# zero_cross_fire_triac.net
KiCad netlist of a schematic drawn in EAGLE
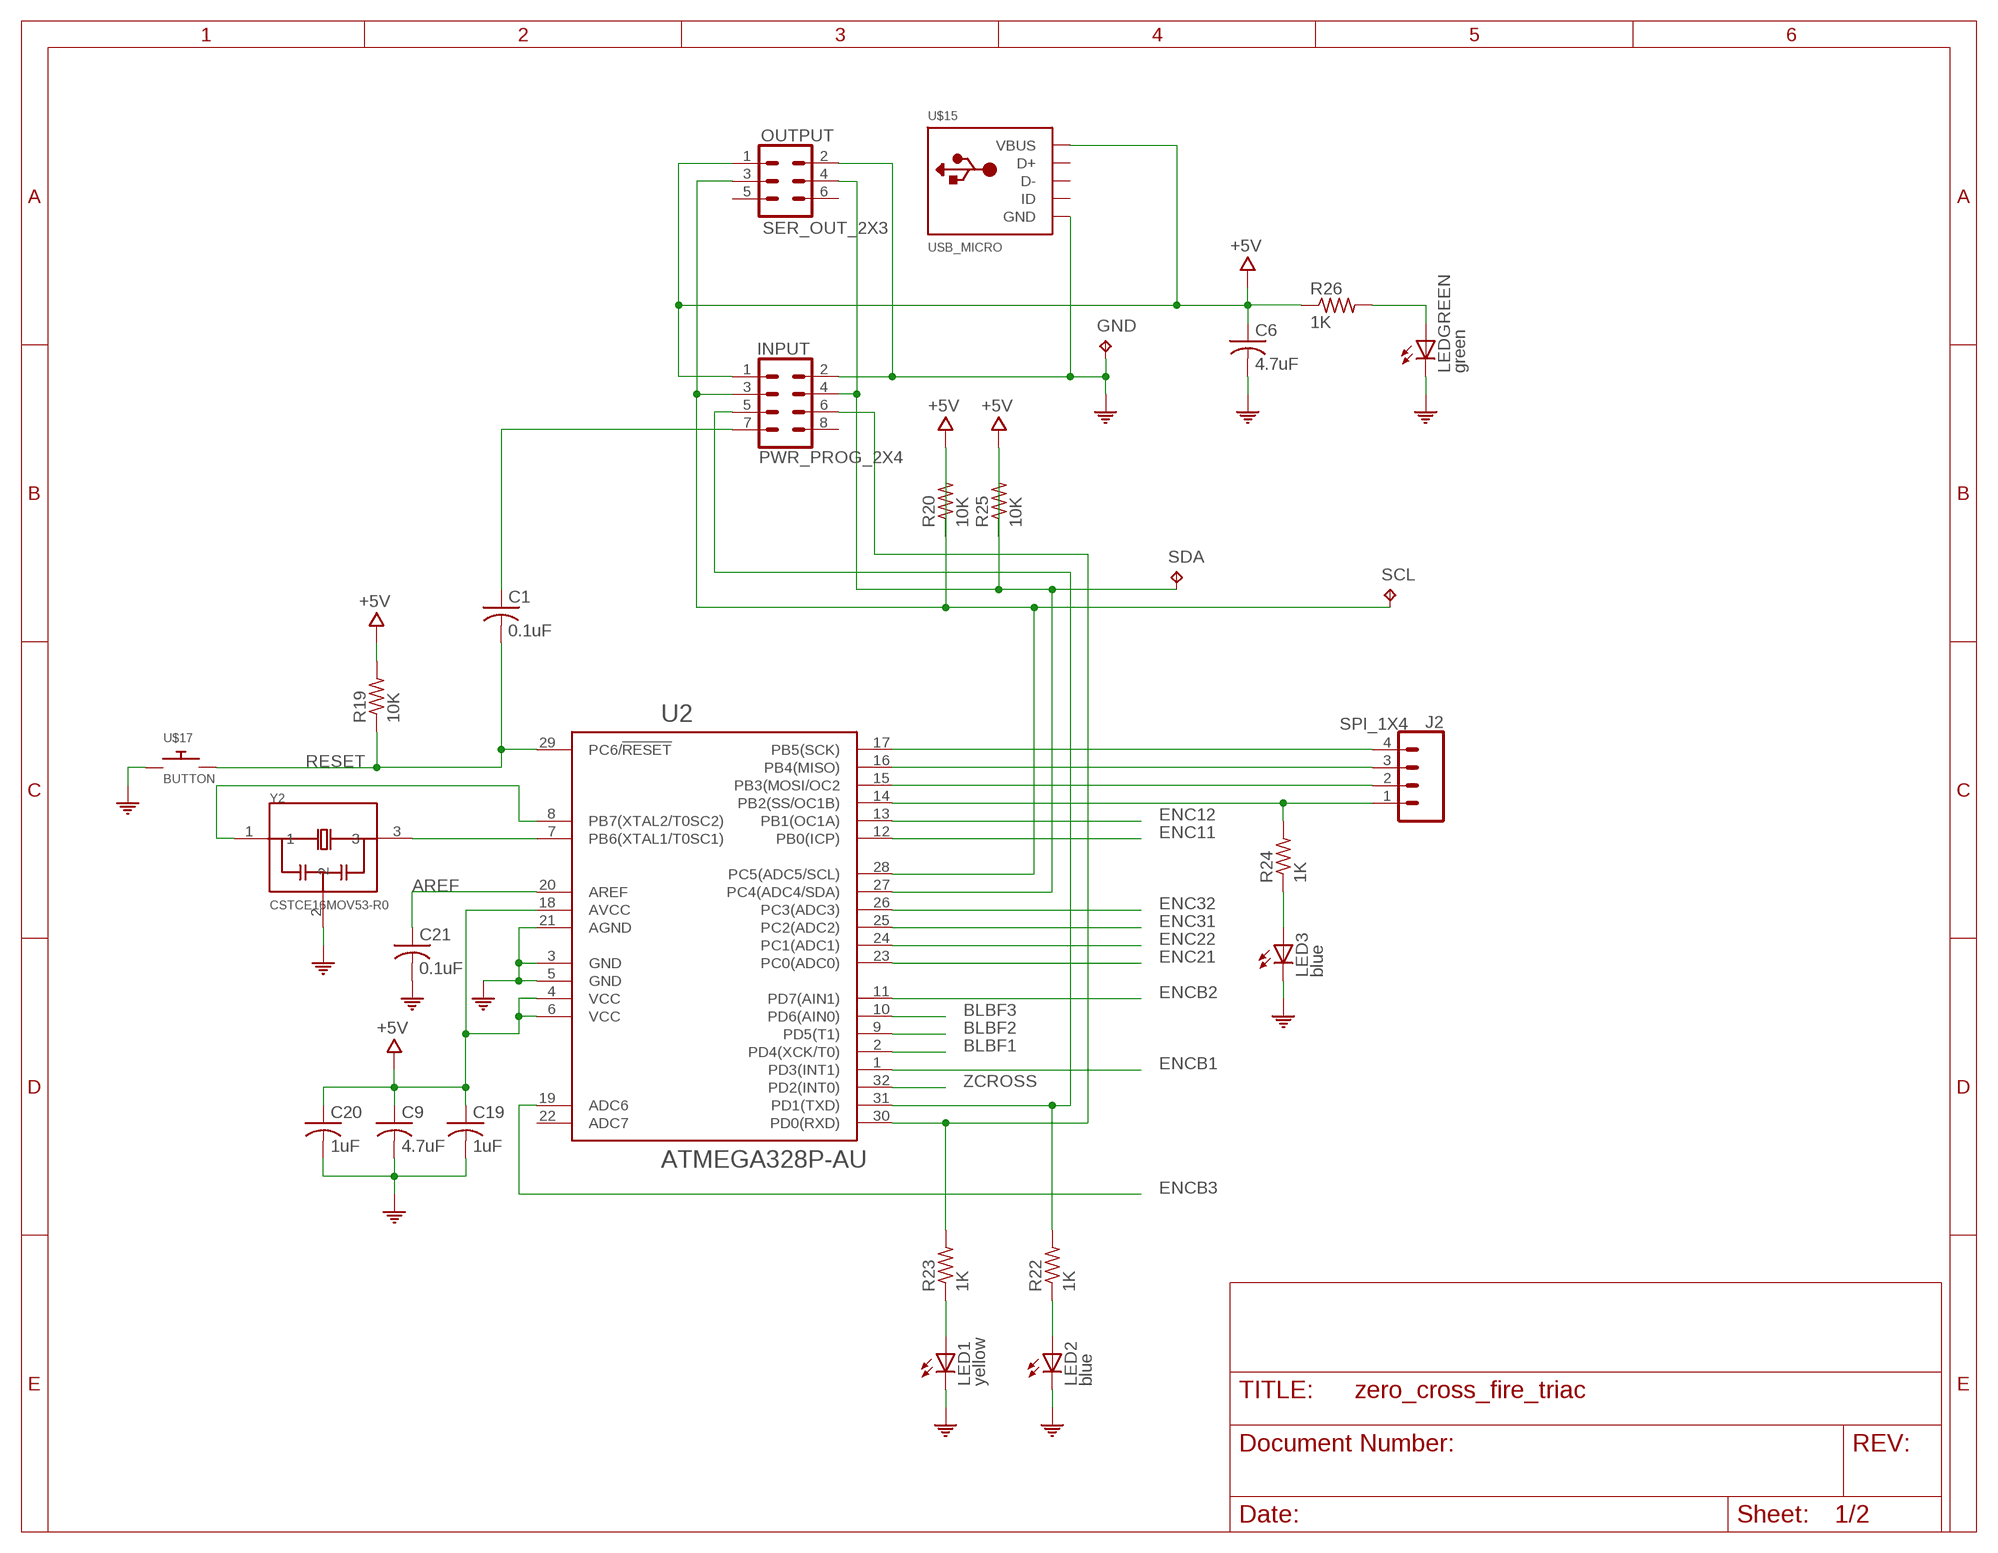
[diagram p0: schematic, sheet 1]
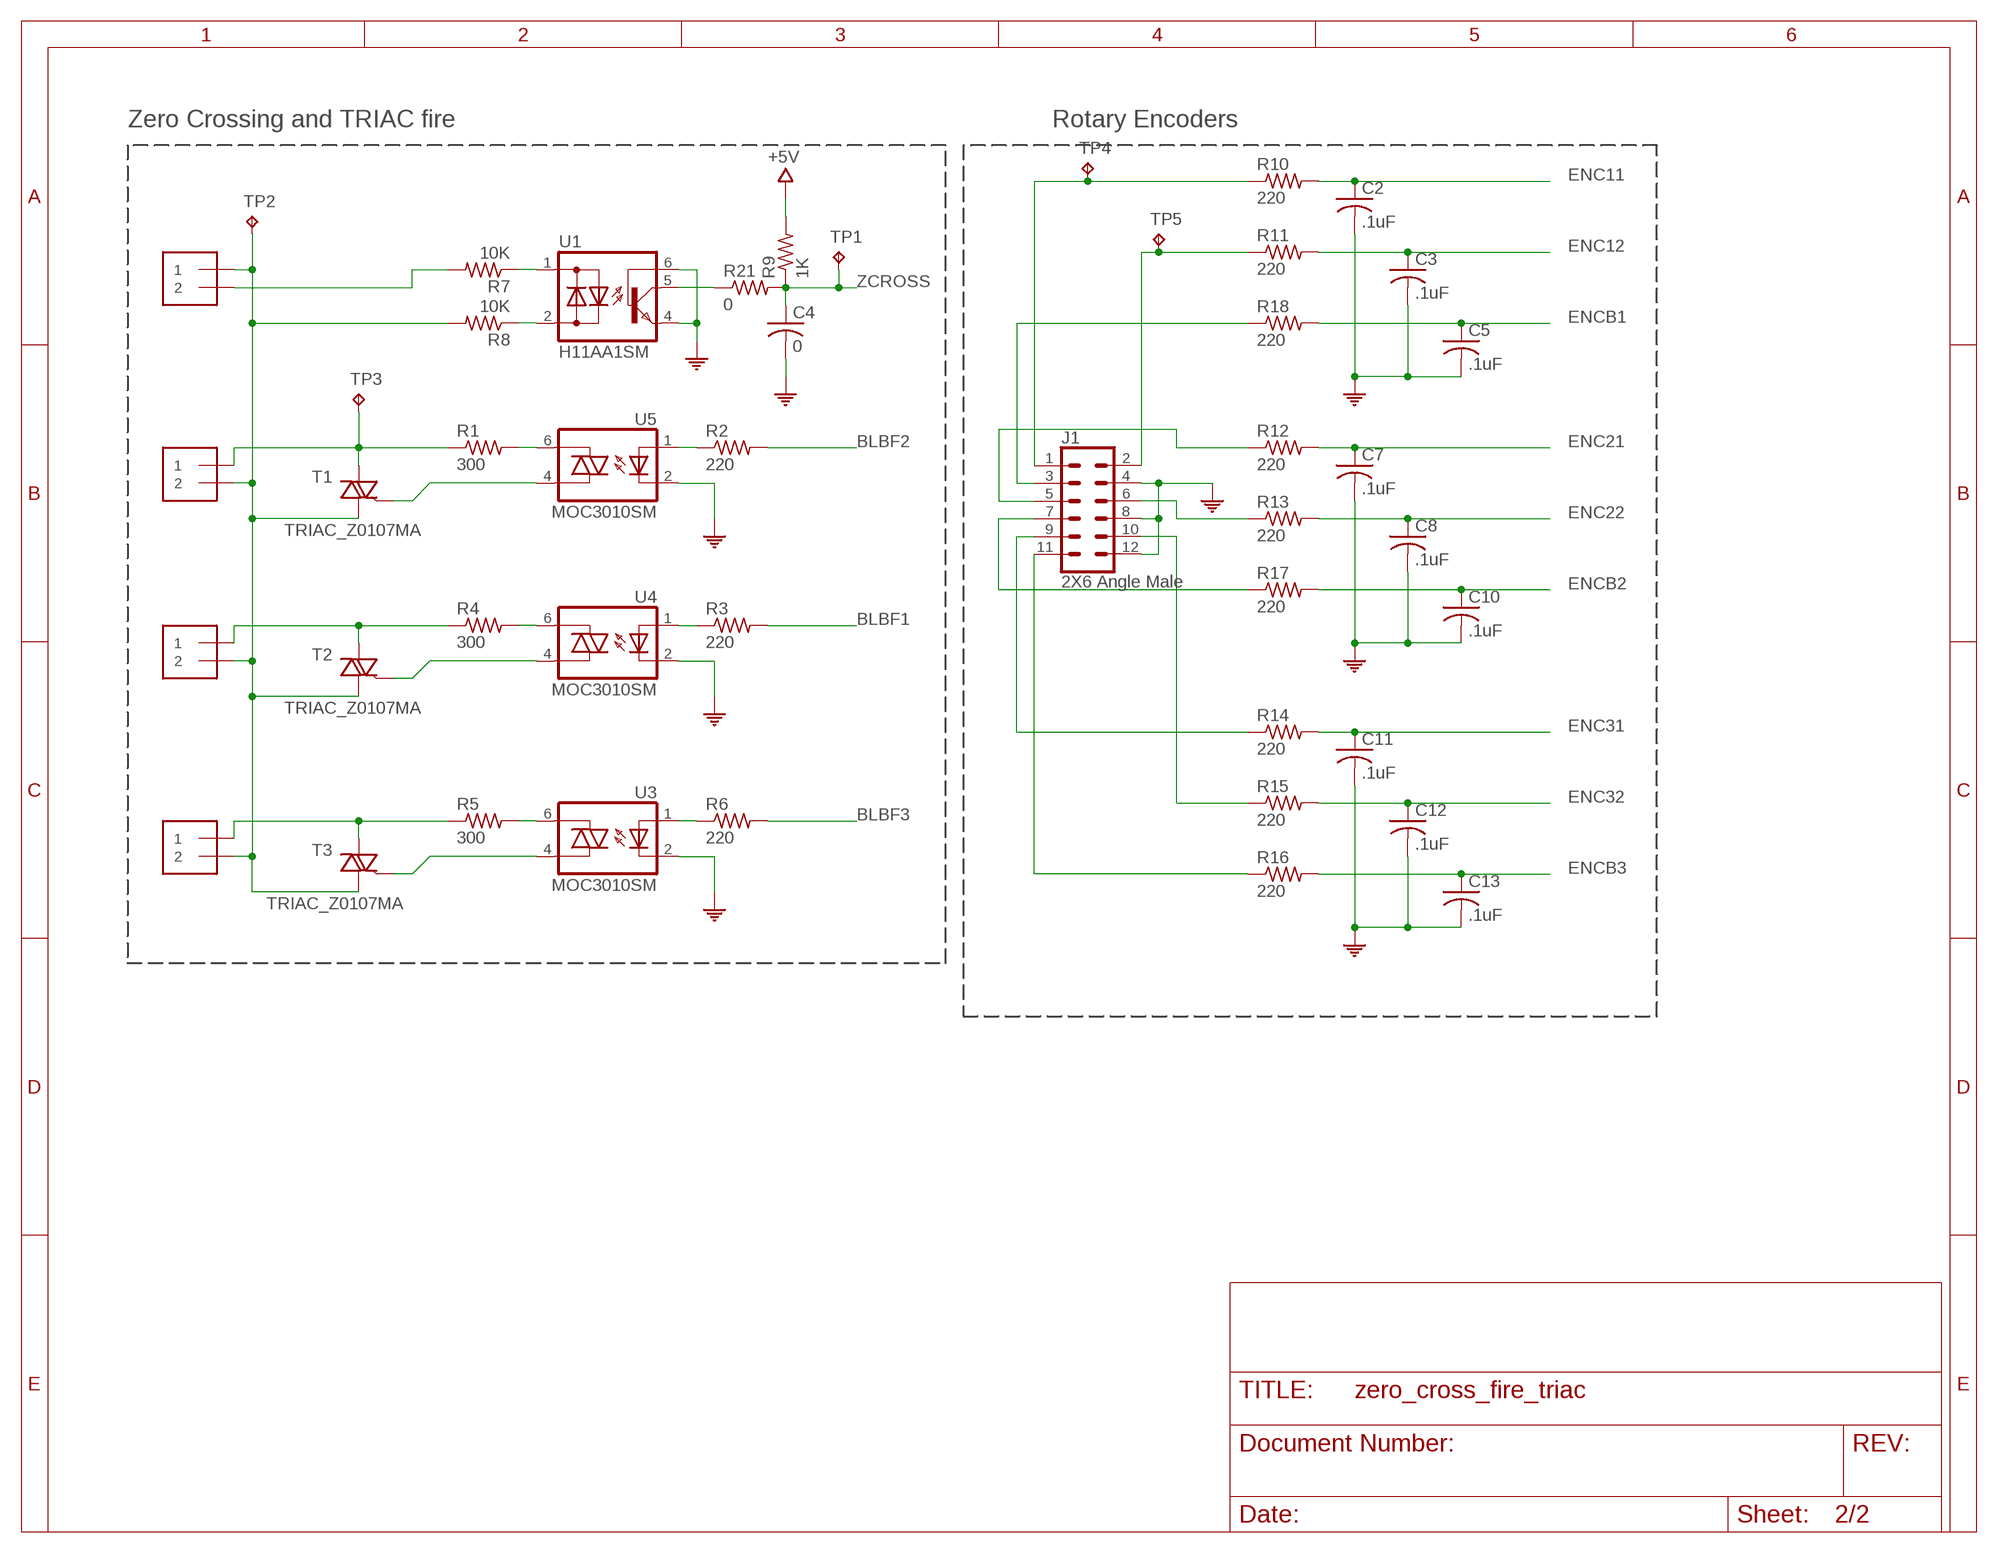
[diagram p1: schematic, sheet 2]

(export (version "E")
  (design (tool "Eeschema 10.0.6"))
  (components
    (comp (ref "C1")
      (value "0.1uF")
      (footprint "eagle-import:C0805")
      (fields (field (name "MF") "TDK") (field (name "MP") "C2012X7R2A104K125AA"))
      (libsource (lib "eagle-import") (part "CAP_C2012X7R2A104K125AA"))
    )
    (comp (ref "C6")
      (value "4.7uF")
      (footprint "eagle-import:C0805")
      (fields (field (name "MF") "KEMET") (field (name "MP") "C0805C475J4RACAUTO"))
      (libsource (lib "eagle-import") (part "CAP_C0805C475J4RACAUTO"))
    )
    (comp (ref "C9")
      (value "4.7uF")
      (footprint "eagle-import:C0805")
      (fields (field (name "MF") "KEMET") (field (name "MP") "C0805C475J4RACAUTO"))
      (libsource (lib "eagle-import") (part "CAP_C0805C475J4RACAUTO"))
    )
    (comp (ref "C19")
      (value "1uF")
      (footprint "eagle-import:C0805")
      (fields (field (name "MF") "TDK") (field (name "MP") " CGA4J1X8R1E105M125AE"))
      (libsource (lib "eagle-import") (part "CAP_CGA4J1X8R1E105M125AE"))
    )
    (comp (ref "C20")
      (value "1uF")
      (footprint "eagle-import:C0805")
      (fields (field (name "MF") "TDK") (field (name "MP") " CGA4J1X8R1E105M125AE"))
      (libsource (lib "eagle-import") (part "CAP_CGA4J1X8R1E105M125AE"))
    )
    (comp (ref "C21")
      (value "0.1uF")
      (footprint "eagle-import:C0805")
      (fields (field (name "MF") "TDK") (field (name "MP") "C2012X7R2A104K125AA"))
      (libsource (lib "eagle-import") (part "CAP_C2012X7R2A104K125AA"))
    )
    (comp (ref "GND")
      (value "TEST_POINT")
      (footprint "eagle-import:TEST")
      (fields (field (name "MF") "Keystone Electronics") (field (name "MP") " 5016"))
      (libsource (lib "eagle-import") (part "TEST_POINT"))
    )
    (comp (ref "INPUT")
      (value "PWR_PROG_2X4")
      (footprint "eagle-import:2X04")
      (fields (field (name "MF") "Adafruit") (field (name "MP") "2x4"))
      (libsource (lib "eagle-import") (part "PWR_PROG_2X4"))
    )
    (comp (ref "J2")
      (value "SPI_1X4")
      (footprint "eagle-import:1X04-BIG")
      (fields (field (name "MF") "adafruit") (field (name "MP") "1x4 "))
      (libsource (lib "eagle-import") (part "SPI_1X4"))
    )
    (comp (ref "LED1")
      (value "yellow")
      (footprint "eagle-import:LED1")
      (fields (field (name "MF") "Kingbright") (field (name "MP") "APTD2012LSYCK"))
      (libsource (lib "eagle-import") (part "LED_APTD2012LSYCK"))
    )
    (comp (ref "LED2")
      (value "blue")
      (footprint "eagle-import:LED1")
      (fields (field (name "MF") "Kingbright") (field (name "MP") "APTD2012LQBC/D"))
      (libsource (lib "eagle-import") (part "LED_APTD2012LQBC"))
    )
    (comp (ref "LED3")
      (value "blue")
      (footprint "eagle-import:LED1")
      (fields (field (name "MF") "Kingbright") (field (name "MP") "APTD2012LQBC/D"))
      (libsource (lib "eagle-import") (part "LED_APTD2012LQBC"))
    )
    (comp (ref "LEDGREEN")
      (value "green")
      (footprint "eagle-import:LED1")
      (fields (field (name "MF") "Kingbright") (field (name "MP") "APTD2012LZGCK"))
      (libsource (lib "eagle-import") (part "LED_APTD2012LZGCK"))
    )
    (comp (ref "OUTPUT")
      (value "SER_OUT_2X3")
      (footprint "eagle-import:2X03")
      (fields (field (name "MF") "adafruit") (field (name "MP") "2x3 female break away"))
      (libsource (lib "eagle-import") (part "SER_OUT_2X3"))
    )
    (comp (ref "R19")
      (value "10K")
      (footprint "eagle-import:R0805")
      (fields (field (name "MF") "Yageo") (field (name "MP") "RC0805JR-7W10KL"))
      (libsource (lib "eagle-import") (part "RESISTOR_RC0805JR-7W10KL"))
    )
    (comp (ref "R20")
      (value "10K")
      (footprint "eagle-import:R0805")
      (fields (field (name "MF") "Yageo") (field (name "MP") "RC0805JR-7W10KL"))
      (libsource (lib "eagle-import") (part "RESISTOR_RC0805JR-7W10KL"))
    )
    (comp (ref "R22")
      (value "1K")
      (footprint "eagle-import:R0805")
      (fields (field (name "MF") "Yageo") (field (name "MP") "RC0805JR-7W1KL"))
      (libsource (lib "eagle-import") (part "RESISTOR_RC0805JR-7W1KL"))
    )
    (comp (ref "R23")
      (value "1K")
      (footprint "eagle-import:R0805")
      (fields (field (name "MF") "Yageo") (field (name "MP") "RC0805JR-7W1KL"))
      (libsource (lib "eagle-import") (part "RESISTOR_RC0805JR-7W1KL"))
    )
    (comp (ref "R24")
      (value "1K")
      (footprint "eagle-import:R0805")
      (fields (field (name "MF") "Yageo") (field (name "MP") "RC0805JR-7W1KL"))
      (libsource (lib "eagle-import") (part "RESISTOR_RC0805JR-7W1KL"))
    )
    (comp (ref "R25")
      (value "10K")
      (footprint "eagle-import:R0805")
      (fields (field (name "MF") "Yageo") (field (name "MP") "RC0805JR-7W10KL"))
      (libsource (lib "eagle-import") (part "RESISTOR_RC0805JR-7W10KL"))
    )
    (comp (ref "R26")
      (value "1K")
      (footprint "eagle-import:R0805")
      (fields (field (name "MF") "Yageo") (field (name "MP") "RC0805JR-7W1KL"))
      (libsource (lib "eagle-import") (part "RESISTOR_RC0805JR-7W1KL"))
    )
    (comp (ref "SCL")
      (value "TEST_POINT")
      (footprint "eagle-import:TEST")
      (fields (field (name "MF") "Keystone Electronics") (field (name "MP") " 5016"))
      (libsource (lib "eagle-import") (part "TEST_POINT"))
    )
    (comp (ref "SDA")
      (value "TEST_POINT")
      (footprint "eagle-import:TEST")
      (fields (field (name "MF") "Keystone Electronics") (field (name "MP") " 5016"))
      (libsource (lib "eagle-import") (part "TEST_POINT"))
    )
    (comp (ref "U$15")
      (value "USB_MICRO")
      (footprint "eagle-import:USB-MICRO-SMD-CUSTOM")
      (libsource (lib "eagle-import") (part "USB_MICRO"))
    )
    (comp (ref "U$17")
      (value "BUTTON")
      (footprint "eagle-import:PUSHBUTTON")
      (fields (field (name "MF") "E-Switch") (field (name "MP") " LL3301FF065QJ"))
      (libsource (lib "eagle-import") (part "BUTTON"))
    )
    (comp (ref "U2")
      (value "ATMEGA328P-AU")
      (footprint "eagle-import:QFP80P900X900X120-32N")
      (fields (field (name "MF") "Microchip"))
      (libsource (lib "eagle-import") (part "ATMEGA328P-AU"))
    )
    (comp (ref "Y2")
      (value "CSTCE16MOV53-R0")
      (footprint "eagle-import:OSC_CSTCE8M00G55-R0")
      (fields (field (name "MF") "Murata Electronics") (field (name "MP") "CSTCE16M0V53-R0"))
      (libsource (lib "eagle-import") (part "CSTCE16MOV53-R0"))
    )
    (comp (ref "BLB1")
      (value "SCREW_BLOCK_2PIN")
      (footprint "eagle-import:1X2-200MIL")
      (libsource (lib "eagle-import") (part "SCREW_BLOCK_2PIN"))
    )
    (comp (ref "BLB2")
      (value "SCREW_BLOCK_2PIN")
      (footprint "eagle-import:1X2-200MIL")
      (libsource (lib "eagle-import") (part "SCREW_BLOCK_2PIN"))
    )
    (comp (ref "BLB3")
      (value "SCREW_BLOCK_2PIN")
      (footprint "eagle-import:1X2-200MIL")
      (libsource (lib "eagle-import") (part "SCREW_BLOCK_2PIN"))
    )
    (comp (ref "C2")
      (value ".1uF")
      (footprint "eagle-import:C0805")
      (fields (field (name "MF") "TDK") (field (name "MP") "C2012X7R2A104K125AA"))
      (libsource (lib "eagle-import") (part "CAP_C2012X7R2A104K125AA"))
    )
    (comp (ref "C3")
      (value ".1uF")
      (footprint "eagle-import:C0805")
      (fields (field (name "MF") "TDK") (field (name "MP") "C2012X7R2A104K125AA"))
      (libsource (lib "eagle-import") (part "CAP_C2012X7R2A104K125AA"))
    )
    (comp (ref "C4")
      (value "0")
      (footprint "eagle-import:C0805")
      (fields (field (name "MF") "TDK") (field (name "MP") "C2012X7R2A104K125AA"))
      (libsource (lib "eagle-import") (part "CAP_C2012X7R2A104K125AA"))
    )
    (comp (ref "C5")
      (value ".1uF")
      (footprint "eagle-import:C0805")
      (fields (field (name "MF") "TDK") (field (name "MP") "C2012X7R2A104K125AA"))
      (libsource (lib "eagle-import") (part "CAP_C2012X7R2A104K125AA"))
    )
    (comp (ref "C7")
      (value ".1uF")
      (footprint "eagle-import:C0805")
      (fields (field (name "MF") "TDK") (field (name "MP") "C2012X7R2A104K125AA"))
      (libsource (lib "eagle-import") (part "CAP_C2012X7R2A104K125AA"))
    )
    (comp (ref "C8")
      (value ".1uF")
      (footprint "eagle-import:C0805")
      (fields (field (name "MF") "TDK") (field (name "MP") "C2012X7R2A104K125AA"))
      (libsource (lib "eagle-import") (part "CAP_C2012X7R2A104K125AA"))
    )
    (comp (ref "C10")
      (value ".1uF")
      (footprint "eagle-import:C0805")
      (fields (field (name "MF") "TDK") (field (name "MP") "C2012X7R2A104K125AA"))
      (libsource (lib "eagle-import") (part "CAP_C2012X7R2A104K125AA"))
    )
    (comp (ref "C11")
      (value ".1uF")
      (footprint "eagle-import:C0805")
      (fields (field (name "MF") "TDK") (field (name "MP") "C2012X7R2A104K125AA"))
      (libsource (lib "eagle-import") (part "CAP_C2012X7R2A104K125AA"))
    )
    (comp (ref "C12")
      (value ".1uF")
      (footprint "eagle-import:C0805")
      (fields (field (name "MF") "TDK") (field (name "MP") "C2012X7R2A104K125AA"))
      (libsource (lib "eagle-import") (part "CAP_C2012X7R2A104K125AA"))
    )
    (comp (ref "C13")
      (value ".1uF")
      (footprint "eagle-import:C0805")
      (fields (field (name "MF") "TDK") (field (name "MP") "C2012X7R2A104K125AA"))
      (libsource (lib "eagle-import") (part "CAP_C2012X7R2A104K125AA"))
    )
    (comp (ref "J1")
      (value "2X6 Angle Male")
      (footprint "eagle-import:2X06")
      (fields (field (name "MF") "Adafruit") (field (name "MP") "2X6 angle"))
      (libsource (lib "eagle-import") (part "ROT_ENCODE_2X6"))
    )
    (comp (ref "MAIN")
      (value "SCREW_BLOCK_2PIN")
      (footprint "eagle-import:1X2-200MIL")
      (libsource (lib "eagle-import") (part "SCREW_BLOCK_2PIN"))
    )
    (comp (ref "R1")
      (value "300")
      (footprint "eagle-import:R1210")
      (fields (field (name "MF") "ROHM Semiconductor") (field (name "MP") " KTR25JZPF3000"))
      (libsource (lib "eagle-import") (part "RESISTOR_KTR25JZPF3000"))
    )
    (comp (ref "R2")
      (value "220")
      (footprint "eagle-import:R0805")
      (fields (field (name "MF") "ROHM Semiconductor") (field (name "MP") "ESR10EZPF2200"))
      (libsource (lib "eagle-import") (part "RESISTOR_ESR10EZPF"))
    )
    (comp (ref "R3")
      (value "220")
      (footprint "eagle-import:R0805")
      (fields (field (name "MF") "ROHM Semiconductor") (field (name "MP") "ESR10EZPF2200"))
      (libsource (lib "eagle-import") (part "RESISTOR_ESR10EZPF"))
    )
    (comp (ref "R4")
      (value "300")
      (footprint "eagle-import:R1210")
      (fields (field (name "MF") "ROHM Semiconductor") (field (name "MP") " KTR25JZPF3000"))
      (libsource (lib "eagle-import") (part "RESISTOR_KTR25JZPF3000"))
    )
    (comp (ref "R5")
      (value "300")
      (footprint "eagle-import:R1210")
      (fields (field (name "MF") "ROHM Semiconductor") (field (name "MP") " KTR25JZPF3000"))
      (libsource (lib "eagle-import") (part "RESISTOR_KTR25JZPF3000"))
    )
    (comp (ref "R6")
      (value "220")
      (footprint "eagle-import:R0805")
      (fields (field (name "MF") "ROHM Semiconductor") (field (name "MP") "ESR10EZPF2200"))
      (libsource (lib "eagle-import") (part "RESISTOR_ESR10EZPF"))
    )
    (comp (ref "R7")
      (value "10K")
      (footprint "eagle-import:RLTR50")
      (fields (field (name "MF") "ROHM Semiconductor") (field (name "MP") " LTR50UZPJ103"))
      (libsource (lib "eagle-import") (part "RESISTOR_LTR50UZPJ"))
    )
    (comp (ref "R8")
      (value "10K")
      (footprint "eagle-import:RLTR50")
      (fields (field (name "MF") "ROHM Semiconductor") (field (name "MP") " LTR50UZPJ103"))
      (libsource (lib "eagle-import") (part "RESISTOR_LTR50UZPJ"))
    )
    (comp (ref "R9")
      (value "1K")
      (footprint "eagle-import:R0805")
      (fields (field (name "MF") "Yageo") (field (name "MP") "RC0805JR-7W1KL"))
      (libsource (lib "eagle-import") (part "RESISTOR_RC0805JR-7W1KL"))
    )
    (comp (ref "R10")
      (value "220")
      (footprint "eagle-import:R0805")
      (fields (field (name "MF") "ROHM Semiconductor") (field (name "MP") "ESR10EZPF2200"))
      (libsource (lib "eagle-import") (part "RESISTOR_ESR10EZPF"))
    )
    (comp (ref "R11")
      (value "220")
      (footprint "eagle-import:R0805")
      (fields (field (name "MF") "ROHM Semiconductor") (field (name "MP") "ESR10EZPF2200"))
      (libsource (lib "eagle-import") (part "RESISTOR_ESR10EZPF"))
    )
    (comp (ref "R12")
      (value "220")
      (footprint "eagle-import:R0805")
      (fields (field (name "MF") "ROHM Semiconductor") (field (name "MP") "ESR10EZPF2200"))
      (libsource (lib "eagle-import") (part "RESISTOR_ESR10EZPF"))
    )
    (comp (ref "R13")
      (value "220")
      (footprint "eagle-import:R0805")
      (fields (field (name "MF") "ROHM Semiconductor") (field (name "MP") "ESR10EZPF2200"))
      (libsource (lib "eagle-import") (part "RESISTOR_ESR10EZPF"))
    )
    (comp (ref "R14")
      (value "220")
      (footprint "eagle-import:R0805")
      (fields (field (name "MF") "ROHM Semiconductor") (field (name "MP") "ESR10EZPF2200"))
      (libsource (lib "eagle-import") (part "RESISTOR_ESR10EZPF"))
    )
    (comp (ref "R15")
      (value "220")
      (footprint "eagle-import:R0805")
      (fields (field (name "MF") "ROHM Semiconductor") (field (name "MP") "ESR10EZPF2200"))
      (libsource (lib "eagle-import") (part "RESISTOR_ESR10EZPF"))
    )
    (comp (ref "R16")
      (value "220")
      (footprint "eagle-import:R0805")
      (fields (field (name "MF") "ROHM Semiconductor") (field (name "MP") "ESR10EZPF2200"))
      (libsource (lib "eagle-import") (part "RESISTOR_ESR10EZPF"))
    )
    (comp (ref "R17")
      (value "220")
      (footprint "eagle-import:R0805")
      (fields (field (name "MF") "ROHM Semiconductor") (field (name "MP") "ESR10EZPF2200"))
      (libsource (lib "eagle-import") (part "RESISTOR_ESR10EZPF"))
    )
    (comp (ref "R18")
      (value "220")
      (footprint "eagle-import:R0805")
      (fields (field (name "MF") "ROHM Semiconductor") (field (name "MP") "ESR10EZPF2200"))
      (libsource (lib "eagle-import") (part "RESISTOR_ESR10EZPF"))
    )
    (comp (ref "R21")
      (value "0")
      (footprint "eagle-import:R0805")
      (fields (field (name "MF") "ROHM Semiconductor") (field (name "MP") "ESR10EZPF2200"))
      (libsource (lib "eagle-import") (part "RESISTOR_ESR10EZPF"))
    )
    (comp (ref "T1")
      (value "TRIAC_Z0107MA")
      (footprint "eagle-import:TO92")
      (fields (field (name "MF") "STMicroelectronics") (field (name "MP") "Z0107MA 5AL2"))
      (libsource (lib "eagle-import") (part "TRIAC_Z0107MA"))
    )
    (comp (ref "T2")
      (value "TRIAC_Z0107MA")
      (footprint "eagle-import:TO92")
      (fields (field (name "MF") "STMicroelectronics") (field (name "MP") "Z0107MA 5AL2"))
      (libsource (lib "eagle-import") (part "TRIAC_Z0107MA"))
    )
    (comp (ref "T3")
      (value "TRIAC_Z0107MA")
      (footprint "eagle-import:TO92")
      (fields (field (name "MF") "STMicroelectronics") (field (name "MP") "Z0107MA 5AL2"))
      (libsource (lib "eagle-import") (part "TRIAC_Z0107MA"))
    )
    (comp (ref "TP1")
      (value "TEST_POINT")
      (footprint "eagle-import:TEST")
      (fields (field (name "MF") "Keystone Electronics") (field (name "MP") " 5016"))
      (libsource (lib "eagle-import") (part "TEST_POINT"))
    )
    (comp (ref "TP2")
      (value "TEST_POINT")
      (footprint "eagle-import:TEST")
      (fields (field (name "MF") "Keystone Electronics") (field (name "MP") " 5016"))
      (libsource (lib "eagle-import") (part "TEST_POINT"))
    )
    (comp (ref "TP3")
      (value "TEST_POINT")
      (footprint "eagle-import:TEST")
      (fields (field (name "MF") "Keystone Electronics") (field (name "MP") " 5016"))
      (libsource (lib "eagle-import") (part "TEST_POINT"))
    )
    (comp (ref "TP4")
      (value "TEST_POINT")
      (footprint "eagle-import:TEST")
      (fields (field (name "MF") "Keystone Electronics") (field (name "MP") " 5016"))
      (libsource (lib "eagle-import") (part "TEST_POINT"))
    )
    (comp (ref "TP5")
      (value "TEST_POINT")
      (footprint "eagle-import:TEST")
      (fields (field (name "MF") "Keystone Electronics") (field (name "MP") " 5016"))
      (libsource (lib "eagle-import") (part "TEST_POINT"))
    )
    (comp (ref "U1")
      (value "H11AA1SM")
      (footprint "eagle-import:DIL6-SMD")
      (fields (field (name "MF") " ON Semiconductor / Fairchild"))
      (libsource (lib "eagle-import") (part "H11AA1SM"))
    )
    (comp (ref "U3")
      (value "MOC3010SM")
      (footprint "eagle-import:DIL6-SMD")
      (fields (field (name "MF") "ON Semiconductor / Fairchild"))
      (libsource (lib "eagle-import") (part "MOC3010SM"))
    )
    (comp (ref "U4")
      (value "MOC3010SM")
      (footprint "eagle-import:DIL6-SMD")
      (fields (field (name "MF") "ON Semiconductor / Fairchild"))
      (libsource (lib "eagle-import") (part "MOC3010SM"))
    )
    (comp (ref "U5")
      (value "MOC3010SM")
      (footprint "eagle-import:DIL6-SMD")
      (fields (field (name "MF") "ON Semiconductor / Fairchild"))
      (libsource (lib "eagle-import") (part "MOC3010SM"))
    )
  )
  (nets
    (net (code "1") (name "+5V") (class "Default")
      (node (ref "C19") (pin "1") (pinfunction "1_1") (pintype "passive"))
      (node (ref "C20") (pin "1") (pinfunction "1_1") (pintype "passive"))
      (node (ref "C6") (pin "1") (pinfunction "1_1") (pintype "passive"))
      (node (ref "C9") (pin "1") (pinfunction "1_1") (pintype "passive"))
      (node (ref "INPUT") (pin "1") (pinfunction "1_1") (pintype "passive"))
      (node (ref "OUTPUT") (pin "1") (pinfunction "1_1") (pintype "bidirectional"))
      (node (ref "R19") (pin "2") (pinfunction "2_2") (pintype "passive"))
      (node (ref "R20") (pin "1") (pinfunction "1_1") (pintype "passive"))
      (node (ref "R25") (pin "1") (pinfunction "1_1") (pintype "passive"))
      (node (ref "R26") (pin "1") (pinfunction "1_1") (pintype "passive"))
      (node (ref "R9") (pin "2") (pinfunction "2_2") (pintype "passive"))
      (node (ref "U$15") (pin "VBUS") (pinfunction "VBUS_VBUS") (pintype "power_in"))
      (node (ref "U2") (pin "18") (pinfunction "AVCC_18") (pintype "power_in"))
      (node (ref "U2") (pin "4") (pinfunction "VCC_4") (pintype "power_in"))
      (node (ref "U2") (pin "6") (pinfunction "VCC_6") (pintype "power_in"))
    )
    (net (code "2") (name "AREF") (class "Default")
      (node (ref "C21") (pin "1") (pinfunction "1_1") (pintype "passive"))
      (node (ref "U2") (pin "20") (pinfunction "AREF_20") (pintype "input"))
    )
    (net (code "3") (name "BLBF1") (class "Default")
      (node (ref "R3") (pin "2") (pinfunction "2_2") (pintype "passive"))
      (node (ref "U2") (pin "2") (pinfunction "PD4(XCK/T0)_2") (pintype "bidirectional"))
    )
    (net (code "4") (name "BLBF2") (class "Default")
      (node (ref "R2") (pin "2") (pinfunction "2_2") (pintype "passive"))
      (node (ref "U2") (pin "9") (pinfunction "PD5(T1)_9") (pintype "bidirectional"))
    )
    (net (code "5") (name "BLBF3") (class "Default")
      (node (ref "R6") (pin "2") (pinfunction "2_2") (pintype "passive"))
      (node (ref "U2") (pin "10") (pinfunction "PD6(AIN0)_10") (pintype "bidirectional"))
    )
    (net (code "6") (name "COM") (class "Default")
      (node (ref "C10") (pin "2") (pinfunction "2_2") (pintype "passive"))
      (node (ref "C11") (pin "2") (pinfunction "2_2") (pintype "passive"))
      (node (ref "C12") (pin "2") (pinfunction "2_2") (pintype "passive"))
      (node (ref "C13") (pin "2") (pinfunction "2_2") (pintype "passive"))
      (node (ref "C19") (pin "2") (pinfunction "2_2") (pintype "passive"))
      (node (ref "C2") (pin "2") (pinfunction "2_2") (pintype "passive"))
      (node (ref "C20") (pin "2") (pinfunction "2_2") (pintype "passive"))
      (node (ref "C21") (pin "2") (pinfunction "2_2") (pintype "passive"))
      (node (ref "C3") (pin "2") (pinfunction "2_2") (pintype "passive"))
      (node (ref "C4") (pin "2") (pinfunction "2_2") (pintype "passive"))
      (node (ref "C5") (pin "2") (pinfunction "2_2") (pintype "passive"))
      (node (ref "C6") (pin "2") (pinfunction "2_2") (pintype "passive"))
      (node (ref "C7") (pin "2") (pinfunction "2_2") (pintype "passive"))
      (node (ref "C8") (pin "2") (pinfunction "2_2") (pintype "passive"))
      (node (ref "C9") (pin "2") (pinfunction "2_2") (pintype "passive"))
      (node (ref "GND") (pin "1") (pinfunction "TP_1") (pintype "input"))
      (node (ref "INPUT") (pin "2") (pinfunction "2_2") (pintype "passive"))
      (node (ref "J1") (pin "12") (pinfunction "12_12") (pintype "passive"))
      (node (ref "J1") (pin "4") (pinfunction "4_4") (pintype "passive"))
      (node (ref "J1") (pin "8") (pinfunction "8_8") (pintype "passive"))
      (node (ref "LED1") (pin "1") (pinfunction "C_1") (pintype "passive"))
      (node (ref "LED2") (pin "1") (pinfunction "C_1") (pintype "passive"))
      (node (ref "LED3") (pin "1") (pinfunction "C_1") (pintype "passive"))
      (node (ref "LEDGREEN") (pin "1") (pinfunction "C_1") (pintype "passive"))
      (node (ref "OUTPUT") (pin "2") (pinfunction "2_2") (pintype "bidirectional"))
      (node (ref "U$15") (pin "GND") (pinfunction "GND_GND") (pintype "power_in"))
      (node (ref "U$15") (pin "SHIELD1") (pinfunction "GND_SHIELD1") (pintype "power_in"))
      (node (ref "U$15") (pin "SHIELD2") (pinfunction "GND_SHIELD2") (pintype "power_in"))
      (node (ref "U$15") (pin "SHIELD3") (pinfunction "GND_SHIELD3") (pintype "power_in"))
      (node (ref "U$17") (pin "1") (pinfunction "P$1_1") (pintype "passive"))
      (node (ref "U$17") (pin "2") (pinfunction "P$1_2") (pintype "passive"))
      (node (ref "U1") (pin "4") (pinfunction "E_4") (pintype "passive"))
      (node (ref "U1") (pin "6") (pinfunction "B_6") (pintype "passive"))
      (node (ref "U2") (pin "21") (pinfunction "AGND_21") (pintype "power_in"))
      (node (ref "U2") (pin "3") (pinfunction "GND_3") (pintype "power_in"))
      (node (ref "U2") (pin "5") (pinfunction "GND_5") (pintype "power_in"))
      (node (ref "U3") (pin "2") (pinfunction "C_2") (pintype "passive"))
      (node (ref "U4") (pin "2") (pinfunction "C_2") (pintype "passive"))
      (node (ref "U5") (pin "2") (pinfunction "C_2") (pintype "passive"))
      (node (ref "Y2") (pin "2") (pinfunction "2_2") (pintype "power_in"))
    )
    (net (code "7") (name "ENC11") (class "Default")
      (node (ref "C2") (pin "1") (pinfunction "1_1") (pintype "passive"))
      (node (ref "R10") (pin "2") (pinfunction "2_2") (pintype "passive"))
      (node (ref "U2") (pin "12") (pinfunction "PB0(ICP)_12") (pintype "bidirectional"))
    )
    (net (code "8") (name "ENC12") (class "Default")
      (node (ref "C3") (pin "1") (pinfunction "1_1") (pintype "passive"))
      (node (ref "R11") (pin "2") (pinfunction "2_2") (pintype "passive"))
      (node (ref "U2") (pin "13") (pinfunction "PB1(OC1A)_13") (pintype "bidirectional"))
    )
    (net (code "9") (name "ENC21") (class "Default")
      (node (ref "C7") (pin "1") (pinfunction "1_1") (pintype "passive"))
      (node (ref "R12") (pin "2") (pinfunction "2_2") (pintype "passive"))
      (node (ref "U2") (pin "23") (pinfunction "PC0(ADC0)_23") (pintype "bidirectional"))
    )
    (net (code "10") (name "ENC22") (class "Default")
      (node (ref "C8") (pin "1") (pinfunction "1_1") (pintype "passive"))
      (node (ref "R13") (pin "2") (pinfunction "2_2") (pintype "passive"))
      (node (ref "U2") (pin "24") (pinfunction "PC1(ADC1)_24") (pintype "bidirectional"))
    )
    (net (code "11") (name "ENC31") (class "Default")
      (node (ref "C11") (pin "1") (pinfunction "1_1") (pintype "passive"))
      (node (ref "R14") (pin "2") (pinfunction "2_2") (pintype "passive"))
      (node (ref "U2") (pin "25") (pinfunction "PC2(ADC2)_25") (pintype "bidirectional"))
    )
    (net (code "12") (name "ENC32") (class "Default")
      (node (ref "C12") (pin "1") (pinfunction "1_1") (pintype "passive"))
      (node (ref "R15") (pin "2") (pinfunction "2_2") (pintype "passive"))
      (node (ref "U2") (pin "26") (pinfunction "PC3(ADC3)_26") (pintype "bidirectional"))
    )
    (net (code "13") (name "ENCB1") (class "Default")
      (node (ref "C5") (pin "1") (pinfunction "1_1") (pintype "passive"))
      (node (ref "R18") (pin "2") (pinfunction "2_2") (pintype "passive"))
      (node (ref "U2") (pin "1") (pinfunction "PD3(INT1)_1") (pintype "bidirectional"))
    )
    (net (code "14") (name "ENCB2") (class "Default")
      (node (ref "C10") (pin "1") (pinfunction "1_1") (pintype "passive"))
      (node (ref "R17") (pin "2") (pinfunction "2_2") (pintype "passive"))
      (node (ref "U2") (pin "11") (pinfunction "PD7(AIN1)_11") (pintype "bidirectional"))
    )
    (net (code "15") (name "ENCB3") (class "Default")
      (node (ref "C13") (pin "1") (pinfunction "1_1") (pintype "passive"))
      (node (ref "R16") (pin "2") (pinfunction "2_2") (pintype "passive"))
      (node (ref "U2") (pin "19") (pinfunction "ADC6_19") (pintype "bidirectional"))
    )
    (net (code "16") (name "Net-(BLB1-1)") (class "Default")
      (node (ref "BLB1") (pin "2") (pinfunction "1_2") (pintype "passive"))
      (node (ref "R4") (pin "1") (pinfunction "1_1") (pintype "passive"))
      (node (ref "T2") (pin "3") (pinfunction "A2_3") (pintype "passive"))
    )
    (net (code "17") (name "Net-(BLB1-2)") (class "Default")
      (node (ref "BLB1") (pin "1") (pinfunction "2_1") (pintype "passive"))
      (node (ref "BLB2") (pin "1") (pinfunction "2_1") (pintype "passive"))
      (node (ref "BLB3") (pin "1") (pinfunction "2_1") (pintype "passive"))
      (node (ref "MAIN") (pin "2") (pinfunction "1_2") (pintype "passive"))
      (node (ref "R8") (pin "P$2") (pinfunction "2_P$2") (pintype "passive"))
      (node (ref "T1") (pin "1") (pinfunction "A1_1") (pintype "passive"))
      (node (ref "T2") (pin "1") (pinfunction "A1_1") (pintype "passive"))
      (node (ref "T3") (pin "1") (pinfunction "A1_1") (pintype "passive"))
      (node (ref "TP2") (pin "1") (pinfunction "TP_1") (pintype "input"))
    )
    (net (code "18") (name "Net-(BLB2-1)") (class "Default")
      (node (ref "BLB2") (pin "2") (pinfunction "1_2") (pintype "passive"))
      (node (ref "R1") (pin "1") (pinfunction "1_1") (pintype "passive"))
      (node (ref "T1") (pin "3") (pinfunction "A2_3") (pintype "passive"))
      (node (ref "TP3") (pin "1") (pinfunction "TP_1") (pintype "input"))
    )
    (net (code "19") (name "Net-(BLB3-1)") (class "Default")
      (node (ref "BLB3") (pin "2") (pinfunction "1_2") (pintype "passive"))
      (node (ref "R5") (pin "1") (pinfunction "1_1") (pintype "passive"))
      (node (ref "T3") (pin "3") (pinfunction "A2_3") (pintype "passive"))
    )
    (net (code "20") (name "Net-(C1-Pad1)") (class "Default")
      (node (ref "C1") (pin "1") (pinfunction "1_1") (pintype "passive"))
      (node (ref "INPUT") (pin "7") (pinfunction "7_7") (pintype "passive"))
    )
    (net (code "21") (name "Net-(J1-Pad3)") (class "Default")
      (node (ref "J1") (pin "3") (pinfunction "3_3") (pintype "passive"))
      (node (ref "R18") (pin "1") (pinfunction "1_1") (pintype "passive"))
    )
    (net (code "22") (name "Net-(J1-Pad5)") (class "Default")
      (node (ref "J1") (pin "5") (pinfunction "5_5") (pintype "passive"))
      (node (ref "R12") (pin "1") (pinfunction "1_1") (pintype "passive"))
    )
    (net (code "23") (name "Net-(J1-Pad6)") (class "Default")
      (node (ref "J1") (pin "6") (pinfunction "6_6") (pintype "passive"))
      (node (ref "R13") (pin "1") (pinfunction "1_1") (pintype "passive"))
    )
    (net (code "24") (name "Net-(J1-Pad7)") (class "Default")
      (node (ref "J1") (pin "7") (pinfunction "7_7") (pintype "passive"))
      (node (ref "R17") (pin "1") (pinfunction "1_1") (pintype "passive"))
    )
    (net (code "25") (name "Net-(J1-Pad9)") (class "Default")
      (node (ref "J1") (pin "9") (pinfunction "9_9") (pintype "passive"))
      (node (ref "R14") (pin "1") (pinfunction "1_1") (pintype "passive"))
    )
    (net (code "26") (name "Net-(J1-Pad10)") (class "Default")
      (node (ref "J1") (pin "10") (pinfunction "10_10") (pintype "passive"))
      (node (ref "R15") (pin "1") (pinfunction "1_1") (pintype "passive"))
    )
    (net (code "27") (name "Net-(J1-Pad11)") (class "Default")
      (node (ref "J1") (pin "11") (pinfunction "11_11") (pintype "passive"))
      (node (ref "R16") (pin "1") (pinfunction "1_1") (pintype "passive"))
    )
    (net (code "28") (name "Net-(LED1-A)") (class "Default")
      (node (ref "LED1") (pin "2") (pinfunction "A_2") (pintype "passive"))
      (node (ref "R23") (pin "1") (pinfunction "1_1") (pintype "passive"))
    )
    (net (code "29") (name "Net-(LED2-A)") (class "Default")
      (node (ref "LED2") (pin "2") (pinfunction "A_2") (pintype "passive"))
      (node (ref "R22") (pin "1") (pinfunction "1_1") (pintype "passive"))
    )
    (net (code "30") (name "Net-(LED3-A)") (class "Default")
      (node (ref "LED3") (pin "2") (pinfunction "A_2") (pintype "passive"))
      (node (ref "R24") (pin "1") (pinfunction "1_1") (pintype "passive"))
    )
    (net (code "31") (name "Net-(LEDGREEN-A)") (class "Default")
      (node (ref "LEDGREEN") (pin "2") (pinfunction "A_2") (pintype "passive"))
      (node (ref "R26") (pin "2") (pinfunction "2_2") (pintype "passive"))
    )
    (net (code "32") (name "Net-(MAIN-2)") (class "Default")
      (node (ref "MAIN") (pin "1") (pinfunction "2_1") (pintype "passive"))
      (node (ref "R7") (pin "P$2") (pinfunction "2_P$2") (pintype "passive"))
    )
    (net (code "33") (name "Net-(R7-1)") (class "Default")
      (node (ref "R7") (pin "P$1") (pinfunction "1_P$1") (pintype "passive"))
      (node (ref "U1") (pin "1") (pinfunction "AC1_1") (pintype "passive"))
    )
    (net (code "34") (name "Net-(R8-1)") (class "Default")
      (node (ref "R8") (pin "P$1") (pinfunction "1_P$1") (pintype "passive"))
      (node (ref "U1") (pin "2") (pinfunction "AC2_2") (pintype "passive"))
    )
    (net (code "35") (name "Net-(SCL-TP)") (class "Default")
      (node (ref "INPUT") (pin "3") (pinfunction "3_3") (pintype "passive"))
      (node (ref "OUTPUT") (pin "3") (pinfunction "3_3") (pintype "bidirectional"))
      (node (ref "R20") (pin "2") (pinfunction "2_2") (pintype "passive"))
      (node (ref "SCL") (pin "1") (pinfunction "TP_1") (pintype "input"))
      (node (ref "U2") (pin "28") (pinfunction "PC5(ADC5/SCL)_28") (pintype "bidirectional"))
    )
    (net (code "36") (name "Net-(SDA-TP)") (class "Default")
      (node (ref "INPUT") (pin "4") (pinfunction "4_4") (pintype "passive"))
      (node (ref "OUTPUT") (pin "4") (pinfunction "4_4") (pintype "bidirectional"))
      (node (ref "R25") (pin "2") (pinfunction "2_2") (pintype "passive"))
      (node (ref "SDA") (pin "1") (pinfunction "TP_1") (pintype "input"))
      (node (ref "U2") (pin "27") (pinfunction "PC4(ADC4/SDA)_27") (pintype "bidirectional"))
    )
    (net (code "37") (name "Net-(T1-G)") (class "Default")
      (node (ref "T1") (pin "2") (pinfunction "G_2") (pintype "passive"))
      (node (ref "U5") (pin "4") (pinfunction "A1_4") (pintype "passive"))
    )
    (net (code "38") (name "Net-(T2-G)") (class "Default")
      (node (ref "T2") (pin "2") (pinfunction "G_2") (pintype "passive"))
      (node (ref "U4") (pin "4") (pinfunction "A1_4") (pintype "passive"))
    )
    (net (code "39") (name "Net-(T3-G)") (class "Default")
      (node (ref "T3") (pin "2") (pinfunction "G_2") (pintype "passive"))
      (node (ref "U3") (pin "4") (pinfunction "A1_4") (pintype "passive"))
    )
    (net (code "40") (name "Net-(TP4-TP)") (class "Default")
      (node (ref "J1") (pin "1") (pinfunction "1_1") (pintype "passive"))
      (node (ref "R10") (pin "1") (pinfunction "1_1") (pintype "passive"))
      (node (ref "TP4") (pin "1") (pinfunction "TP_1") (pintype "input"))
    )
    (net (code "41") (name "Net-(TP5-TP)") (class "Default")
      (node (ref "J1") (pin "2") (pinfunction "2_2") (pintype "passive"))
      (node (ref "R11") (pin "1") (pinfunction "1_1") (pintype "passive"))
      (node (ref "TP5") (pin "1") (pinfunction "TP_1") (pintype "input"))
    )
    (net (code "42") (name "Net-(U1-C)") (class "Default")
      (node (ref "R21") (pin "1") (pinfunction "1_1") (pintype "passive"))
      (node (ref "U1") (pin "5") (pinfunction "C_5") (pintype "passive"))
    )
    (net (code "43") (name "Net-(U2-PB2(SS{slash}OC1B))") (class "Default")
      (node (ref "J2") (pin "1") (pinfunction "1_1") (pintype "passive"))
      (node (ref "R24") (pin "2") (pinfunction "2_2") (pintype "passive"))
      (node (ref "U2") (pin "14") (pinfunction "PB2(SS/OC1B)_14") (pintype "bidirectional"))
    )
    (net (code "44") (name "Net-(U2-PB3(MOSI{slash}OC2)") (class "Default")
      (node (ref "J2") (pin "2") (pinfunction "2_2") (pintype "passive"))
      (node (ref "U2") (pin "15") (pinfunction "PB3(MOSI/OC2_15") (pintype "bidirectional"))
    )
    (net (code "45") (name "Net-(U2-PB4(MISO))") (class "Default")
      (node (ref "J2") (pin "3") (pinfunction "3_3") (pintype "passive"))
      (node (ref "U2") (pin "16") (pinfunction "PB4(MISO)_16") (pintype "bidirectional"))
    )
    (net (code "46") (name "Net-(U2-PB5(SCK))") (class "Default")
      (node (ref "J2") (pin "4") (pinfunction "4_4") (pintype "passive"))
      (node (ref "U2") (pin "17") (pinfunction "PB5(SCK)_17") (pintype "bidirectional"))
    )
    (net (code "47") (name "Net-(U2-PB6(XTAL1{slash}T0SC1))") (class "Default")
      (node (ref "U2") (pin "7") (pinfunction "PB6(XTAL1/T0SC1)_7") (pintype "bidirectional"))
      (node (ref "Y2") (pin "3") (pinfunction "3_3") (pintype "passive"))
    )
    (net (code "48") (name "Net-(U2-PB7(XTAL2{slash}T0SC2))") (class "Default")
      (node (ref "U2") (pin "8") (pinfunction "PB7(XTAL2/T0SC2)_8") (pintype "bidirectional"))
      (node (ref "Y2") (pin "1") (pinfunction "1_1") (pintype "passive"))
    )
    (net (code "49") (name "Net-(U2-PD0(RXD))") (class "Default")
      (node (ref "INPUT") (pin "6") (pinfunction "6_6") (pintype "passive"))
      (node (ref "R23") (pin "2") (pinfunction "2_2") (pintype "passive"))
      (node (ref "U2") (pin "30") (pinfunction "PD0(RXD)_30") (pintype "bidirectional"))
    )
    (net (code "50") (name "Net-(U2-PD1(TXD))") (class "Default")
      (node (ref "INPUT") (pin "5") (pinfunction "5_5") (pintype "passive"))
      (node (ref "R22") (pin "2") (pinfunction "2_2") (pintype "passive"))
      (node (ref "U2") (pin "31") (pinfunction "PD1(TXD)_31") (pintype "bidirectional"))
    )
    (net (code "51") (name "Net-(U3-A)") (class "Default")
      (node (ref "R6") (pin "1") (pinfunction "1_1") (pintype "passive"))
      (node (ref "U3") (pin "1") (pinfunction "A_1") (pintype "passive"))
    )
    (net (code "52") (name "Net-(U3-A2)") (class "Default")
      (node (ref "R5") (pin "2") (pinfunction "2_2") (pintype "passive"))
      (node (ref "U3") (pin "6") (pinfunction "A2_6") (pintype "passive"))
    )
    (net (code "53") (name "Net-(U4-A)") (class "Default")
      (node (ref "R3") (pin "1") (pinfunction "1_1") (pintype "passive"))
      (node (ref "U4") (pin "1") (pinfunction "A_1") (pintype "passive"))
    )
    (net (code "54") (name "Net-(U4-A2)") (class "Default")
      (node (ref "R4") (pin "2") (pinfunction "2_2") (pintype "passive"))
      (node (ref "U4") (pin "6") (pinfunction "A2_6") (pintype "passive"))
    )
    (net (code "55") (name "Net-(U5-A)") (class "Default")
      (node (ref "R2") (pin "1") (pinfunction "1_1") (pintype "passive"))
      (node (ref "U5") (pin "1") (pinfunction "A_1") (pintype "passive"))
    )
    (net (code "56") (name "Net-(U5-A2)") (class "Default")
      (node (ref "R1") (pin "2") (pinfunction "2_2") (pintype "passive"))
      (node (ref "U5") (pin "6") (pinfunction "A2_6") (pintype "passive"))
    )
    (net (code "57") (name "RESET") (class "Default")
      (node (ref "C1") (pin "2") (pinfunction "2_2") (pintype "passive"))
      (node (ref "R19") (pin "1") (pinfunction "1_1") (pintype "passive"))
      (node (ref "U$17") (pin "3") (pinfunction "P$2_3") (pintype "passive"))
      (node (ref "U$17") (pin "4") (pinfunction "P$2_4") (pintype "passive"))
      (node (ref "U2") (pin "29") (pinfunction "PC6/~{RESET}_29") (pintype "bidirectional"))
    )
    (net (code "58") (name "ZCROSS") (class "Default")
      (node (ref "C4") (pin "1") (pinfunction "1_1") (pintype "passive"))
      (node (ref "R21") (pin "2") (pinfunction "2_2") (pintype "passive"))
      (node (ref "R9") (pin "1") (pinfunction "1_1") (pintype "passive"))
      (node (ref "TP1") (pin "1") (pinfunction "TP_1") (pintype "input"))
      (node (ref "U2") (pin "32") (pinfunction "PD2(INT0)_32") (pintype "bidirectional"))
    )
    (net (code "59") (name "unconnected-(INPUT-Pad8)") (class "Default")
      (node (ref "INPUT") (pin "8") (pinfunction "8_8") (pintype "passive"))
    )
    (net (code "60") (name "unconnected-(OUTPUT-Pad5)") (class "Default")
      (node (ref "OUTPUT") (pin "5") (pinfunction "5_5") (pintype "bidirectional"))
    )
    (net (code "61") (name "unconnected-(OUTPUT-Pad6)") (class "Default")
      (node (ref "OUTPUT") (pin "6") (pinfunction "6_6") (pintype "bidirectional"))
    )
    (net (code "62") (name "unconnected-(U$15-PadD+)") (class "Default")
      (node (ref "U$15") (pin "D+") (pinfunction "D+_D+") (pintype "bidirectional"))
    )
    (net (code "63") (name "unconnected-(U$15-PadD-)") (class "Default")
      (node (ref "U$15") (pin "D-") (pinfunction "D-_D-") (pintype "bidirectional"))
    )
    (net (code "64") (name "unconnected-(U$15-PadID)") (class "Default")
      (node (ref "U$15") (pin "ID") (pinfunction "ID_ID") (pintype "bidirectional"))
    )
    (net (code "65") (name "unconnected-(U2-ADC7-Pad22)") (class "Default")
      (node (ref "U2") (pin "22") (pinfunction "ADC7_22") (pintype "bidirectional"))
    )
  )
)
